# OpenRTVC_Allumage_Moteur.net
KiCad netlist of a schematic drawn in EasyEDA
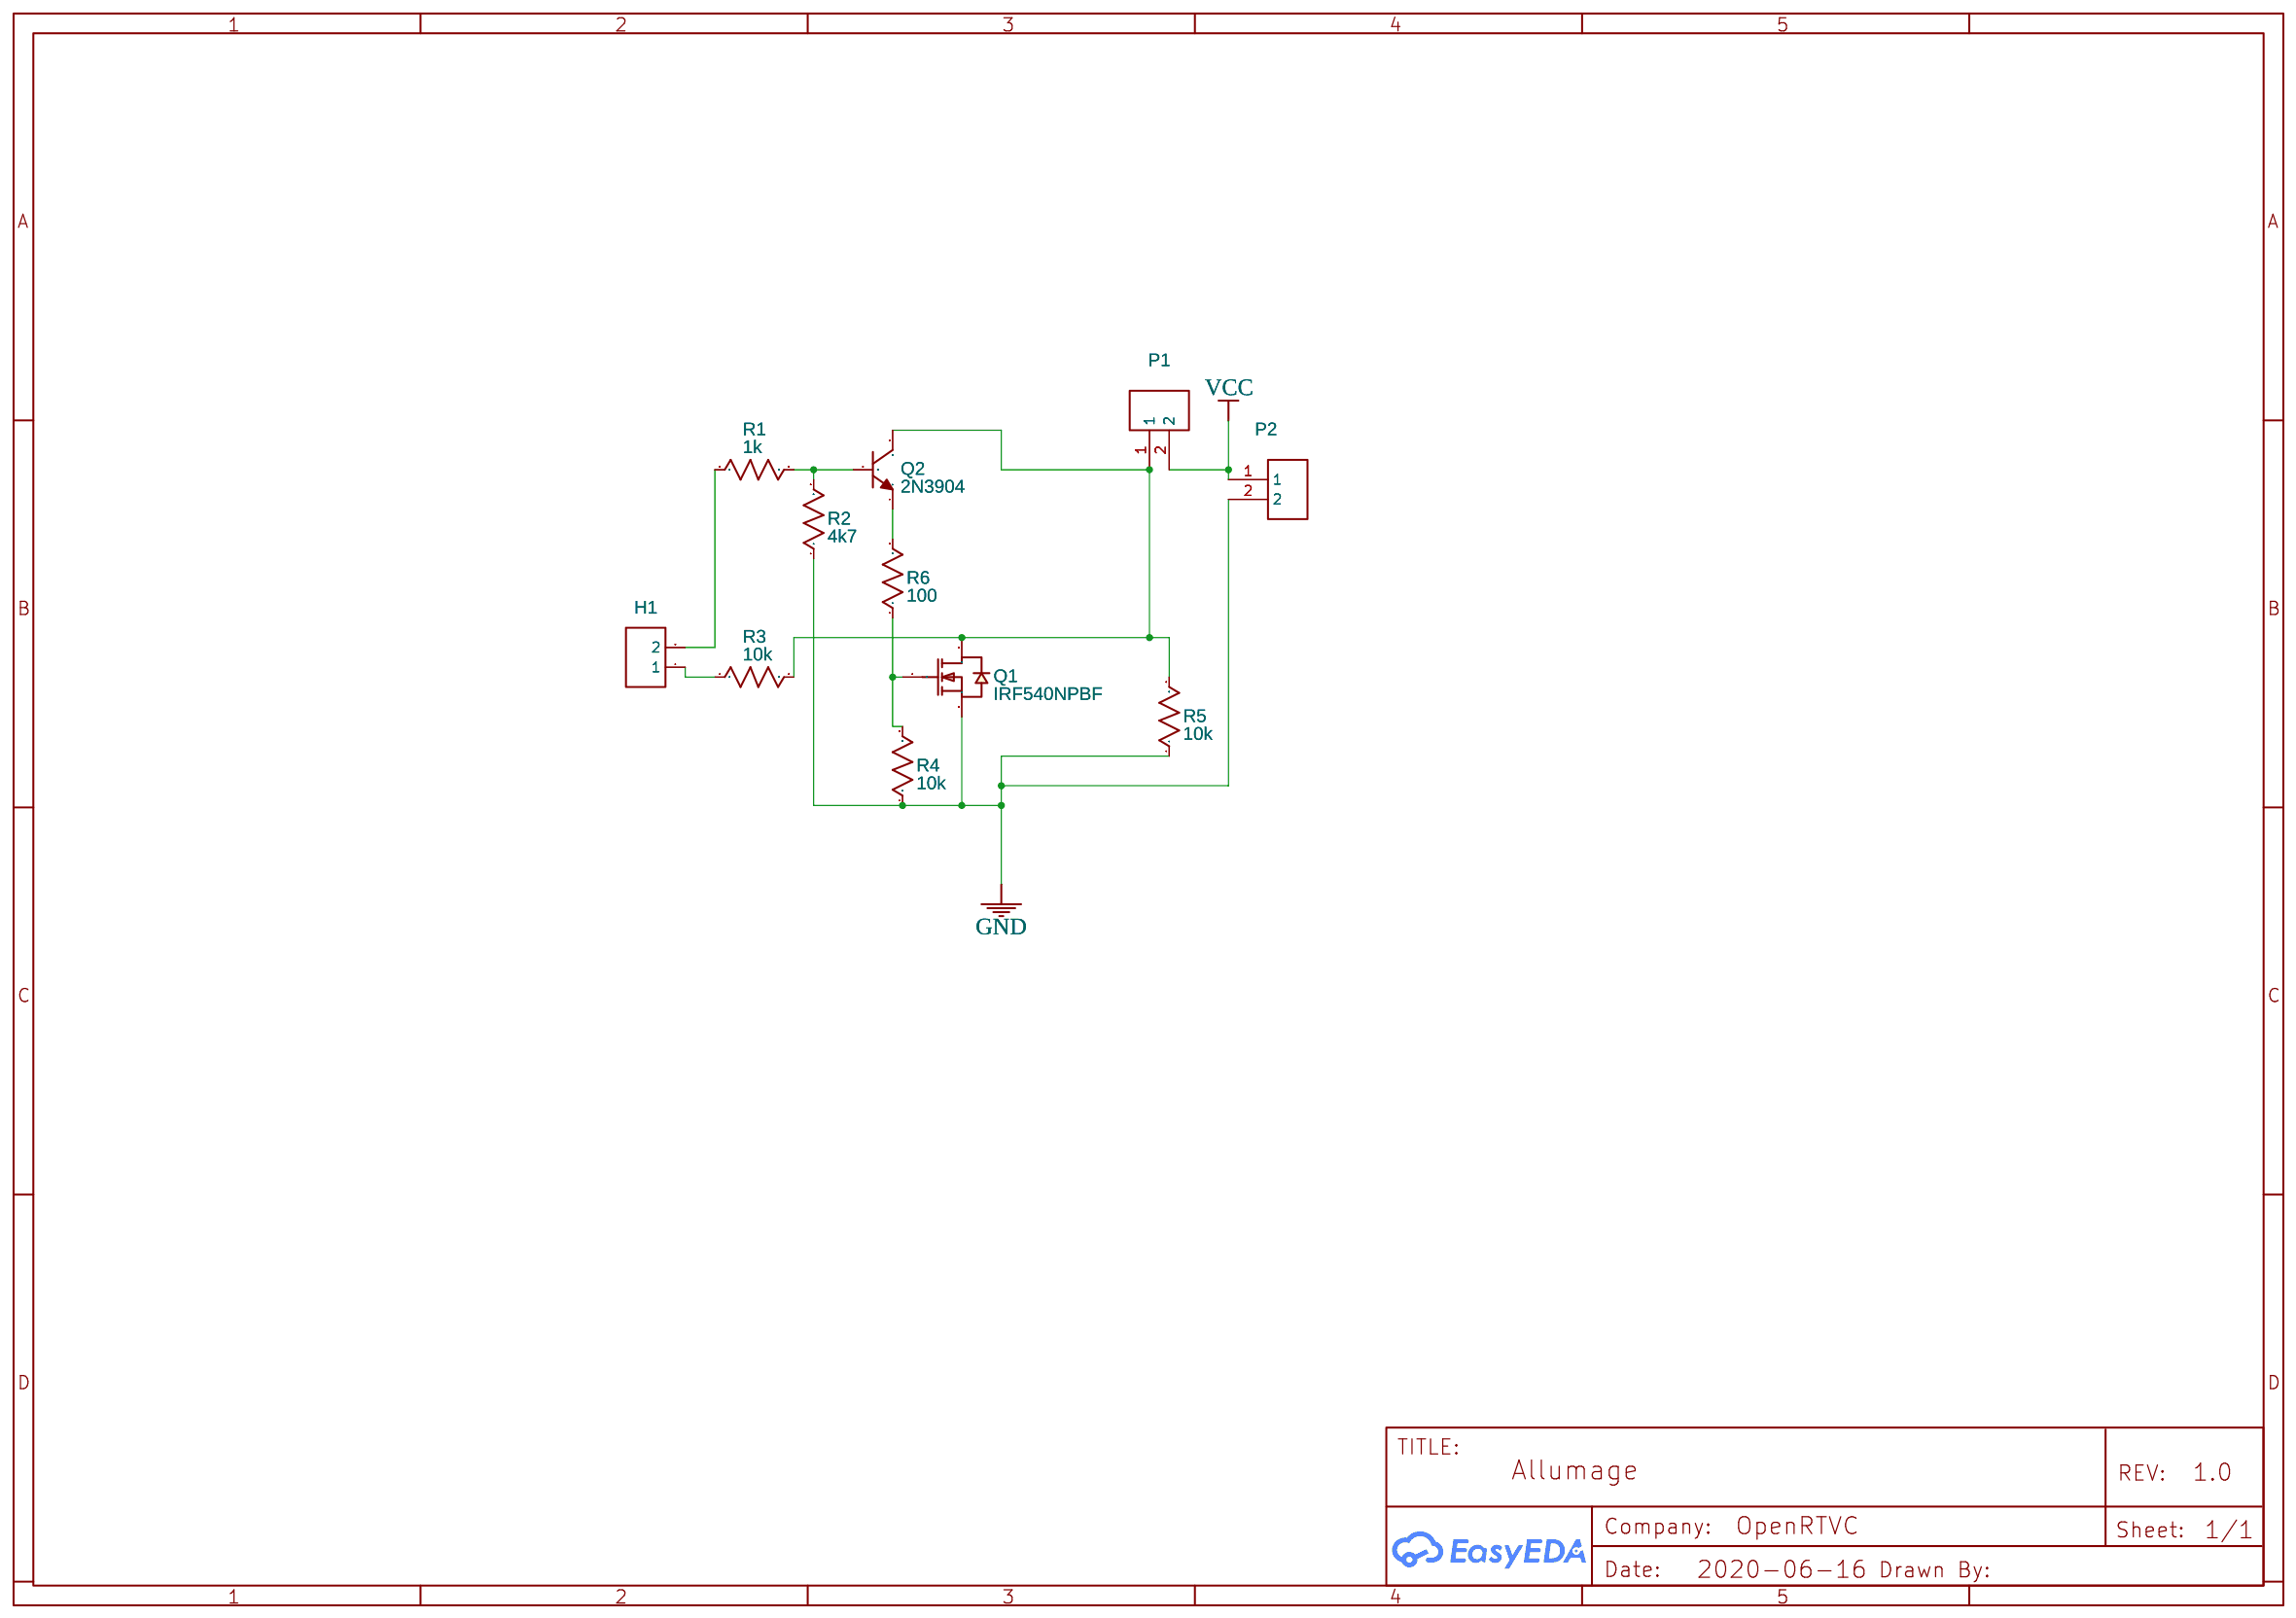
[diagram p0: schematic sheet]

(export (version "E")
  (design (tool "Eeschema 10.0.6"))
  (components
    (comp (ref "H1")
      (value "HDR-F-2.54_1x2")
      (fields (field (name "BOM_Supplier Part") "C49661"))
      (libsource (lib "") (part "HDR-F-2.54_1x2"))
    )
    (comp (ref "P1")
      (value "WJ301V-5.0-2P")
      (fields (field (name "BOM_Supplier Part") "C8475"))
      (libsource (lib "") (part "WJ301V-5.0-2P"))
    )
    (comp (ref "P2")
      (value "WJ301V-5.0-2P")
      (fields (field (name "BOM_Supplier Part") "C8475"))
      (libsource (lib "") (part "WJ301V-5.0-2P_1"))
    )
    (comp (ref "Q1")
      (value "IRF540NPBF")
      (fields (field (name "BOM_Supplier Part") "C2566"))
      (libsource (lib "") (part "IRF540NPBF"))
    )
    (comp (ref "Q2")
      (value "2N3904")
      (fields (field (name "BOM_Supplier Part") "C118538"))
      (libsource (lib "") (part "2N3904"))
    )
    (comp (ref "R1") (value "1k") (libsource (lib "") (part "R_0201_US_1")))
    (comp (ref "R2") (value "4k7") (libsource (lib "") (part "R_0201_US")))
    (comp (ref "R3") (value "10k") (libsource (lib "") (part "R_0201_US_1")))
    (comp (ref "R4") (value "10k") (libsource (lib "") (part "R_0201_US")))
    (comp (ref "R5") (value "10k") (libsource (lib "") (part "R_0201_US")))
    (comp (ref "R6") (value "100") (libsource (lib "") (part "R_0201_US")))
  )
  (nets
    (net (code "1") (name "GND") (class "Default")
      (node (ref "P2") (pin "2") (pinfunction "2_2") (pintype "unspecified"))
      (node (ref "Q1") (pin "3") (pinfunction "S_3") (pintype "unspecified"))
      (node (ref "R2") (pin "1") (pinfunction "1_1") (pintype "unspecified"))
      (node (ref "R4") (pin "1") (pinfunction "1_1") (pintype "unspecified"))
      (node (ref "R5") (pin "1") (pinfunction "1_1") (pintype "unspecified"))
    )
    (net (code "2") (name "Net-(H1-Pad1)") (class "Default")
      (node (ref "H1") (pin "1") (pinfunction "1_1") (pintype "input"))
      (node (ref "R3") (pin "1") (pinfunction "1_1") (pintype "unspecified"))
    )
    (net (code "3") (name "Net-(H1-Pad2)") (class "Default")
      (node (ref "H1") (pin "2") (pinfunction "2_2") (pintype "input"))
      (node (ref "R1") (pin "1") (pinfunction "1_1") (pintype "unspecified"))
    )
    (net (code "4") (name "Net-(Q1-D)") (class "Default")
      (node (ref "P1") (pin "1") (pinfunction "1_1") (pintype "unspecified"))
      (node (ref "Q1") (pin "2") (pinfunction "D_2") (pintype "unspecified"))
      (node (ref "Q2") (pin "3") (pinfunction "C_3") (pintype "unspecified"))
      (node (ref "R3") (pin "2") (pinfunction "2_2") (pintype "unspecified"))
      (node (ref "R5") (pin "2") (pinfunction "2_2") (pintype "unspecified"))
    )
    (net (code "5") (name "Net-(Q1-G)") (class "Default")
      (node (ref "Q1") (pin "1") (pinfunction "G_1") (pintype "unspecified"))
      (node (ref "R4") (pin "2") (pinfunction "2_2") (pintype "unspecified"))
      (node (ref "R6") (pin "1") (pinfunction "1_1") (pintype "unspecified"))
    )
    (net (code "6") (name "Net-(Q2-B)") (class "Default")
      (node (ref "Q2") (pin "2") (pinfunction "B_2") (pintype "unspecified"))
      (node (ref "R1") (pin "2") (pinfunction "2_2") (pintype "unspecified"))
      (node (ref "R2") (pin "2") (pinfunction "2_2") (pintype "unspecified"))
    )
    (net (code "7") (name "Net-(Q2-E)") (class "Default")
      (node (ref "Q2") (pin "1") (pinfunction "E_1") (pintype "unspecified"))
      (node (ref "R6") (pin "2") (pinfunction "2_2") (pintype "unspecified"))
    )
    (net (code "8") (name "VCC") (class "Default")
      (node (ref "P1") (pin "2") (pinfunction "2_2") (pintype "unspecified"))
      (node (ref "P2") (pin "1") (pinfunction "1_1") (pintype "unspecified"))
    )
  )
)
